# button3.net
KiCad netlist of a schematic drawn in Altium Designer
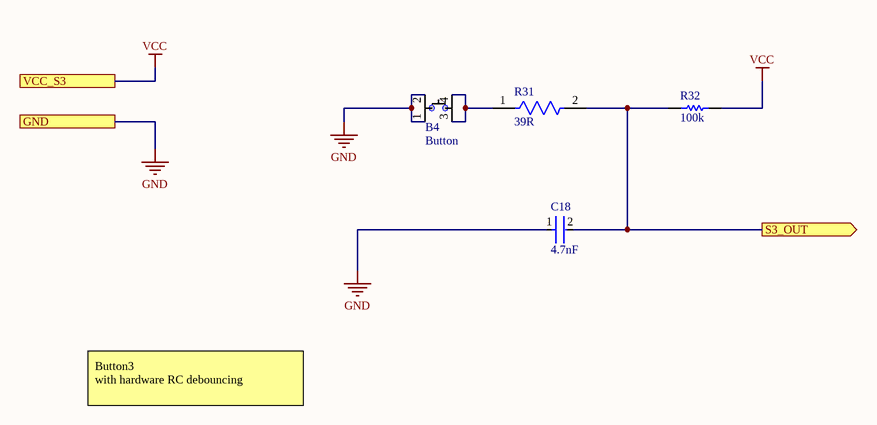
[diagram p0: button3.SchDoc]

(export (version "E")
  (design (tool "Eeschema 10.0.6"))
  (components
    (comp (ref "B4")
      (value "Button")
      (footprint "PTS810 SJK 250 SMTR LFS")
      (description "SWITCH TACTILE SPST-NO 0.05A 16V Tactile Switch SPST-NO Top Actuated Surface Mount")
      (fields
        (field (name "MANUFACTURER") "ITT /  C&K Components")
        (field (name "MANUFACTURER PART NUMBER") "PTS810SJK250SMTRLFS")
      )
      (libsource (lib "Schematics") (part "PTS810 SJK 250 SMTR LFS"))
    )
    (comp (ref "C18")
      (value "4.7nF")
      (footprint "FP-0603-L_1_6_0_15-W_0_81-MFG")
      (description "General Purpose Ceramic Capacitor, 0603, 4.7nF, 10%, X7R, 15%, 50V")
      (fields (field (name "VOLTAGE") "50V") (field (name "TOLERANCE") "10%"))
      (libsource (lib "Altium Content Vault") (part "02cd4be3c70576c341d710602a673aa"))
    )
    (comp (ref "R31")
      (value "39R")
      (footprint "FP-CPF0603-MFG")
      (description "RES SMD 39Ω 0.1% 1/16W 0603")
      (fields
        (field (name "TOLERANCE") "0.1%")
        (field (name "OCTOPART") "https://octopart.com/cpf0603b39re1-te+connectivity-9539401")
      )
      (libsource (lib "Altium Content Vault") (part "1029c3af85768c4190bb7ad29bc67b5"))
    )
    (comp (ref "R32")
      (value "100k")
      (footprint "RESC1609X55X30ML10T20")
      (fields (field (name "MANUFACTURER") "Vishay Dale") (field (name "PART NUMBER") "TNPW0603100KBEEA"))
      (libsource (lib "Altium Content Vault") (part "RES"))
    )
  )
  (nets
    (net (code "1") (name "/S3_OUT") (class "Default")
      (node (ref "C18") (pin "2") (pinfunction "2_2") (pintype "passive"))
      (node (ref "R31") (pin "2") (pinfunction "2_2") (pintype "passive"))
      (node (ref "R32") (pin "1") (pinfunction "1_1") (pintype "passive"))
    )
    (net (code "2") (name "GND") (class "Default")
      (node (ref "B4") (pin "1") (pinfunction "1_1") (pintype "power_in"))
      (node (ref "B4") (pin "2") (pinfunction "2_2") (pintype "power_in"))
      (node (ref "C18") (pin "1") (pinfunction "1_1") (pintype "passive"))
    )
    (net (code "3") (name "Net-(B4-Pad3)") (class "Default")
      (node (ref "B4") (pin "3") (pinfunction "3_3") (pintype "power_in"))
      (node (ref "B4") (pin "4") (pinfunction "4_4") (pintype "power_in"))
      (node (ref "R31") (pin "1") (pinfunction "1_1") (pintype "passive"))
    )
    (net (code "4") (name "VCC") (class "Default")
      (node (ref "R32") (pin "2") (pinfunction "2_2") (pintype "passive"))
    )
  )
)
